# Panel.net
KiCad netlist of a schematic drawn in Altium Designer
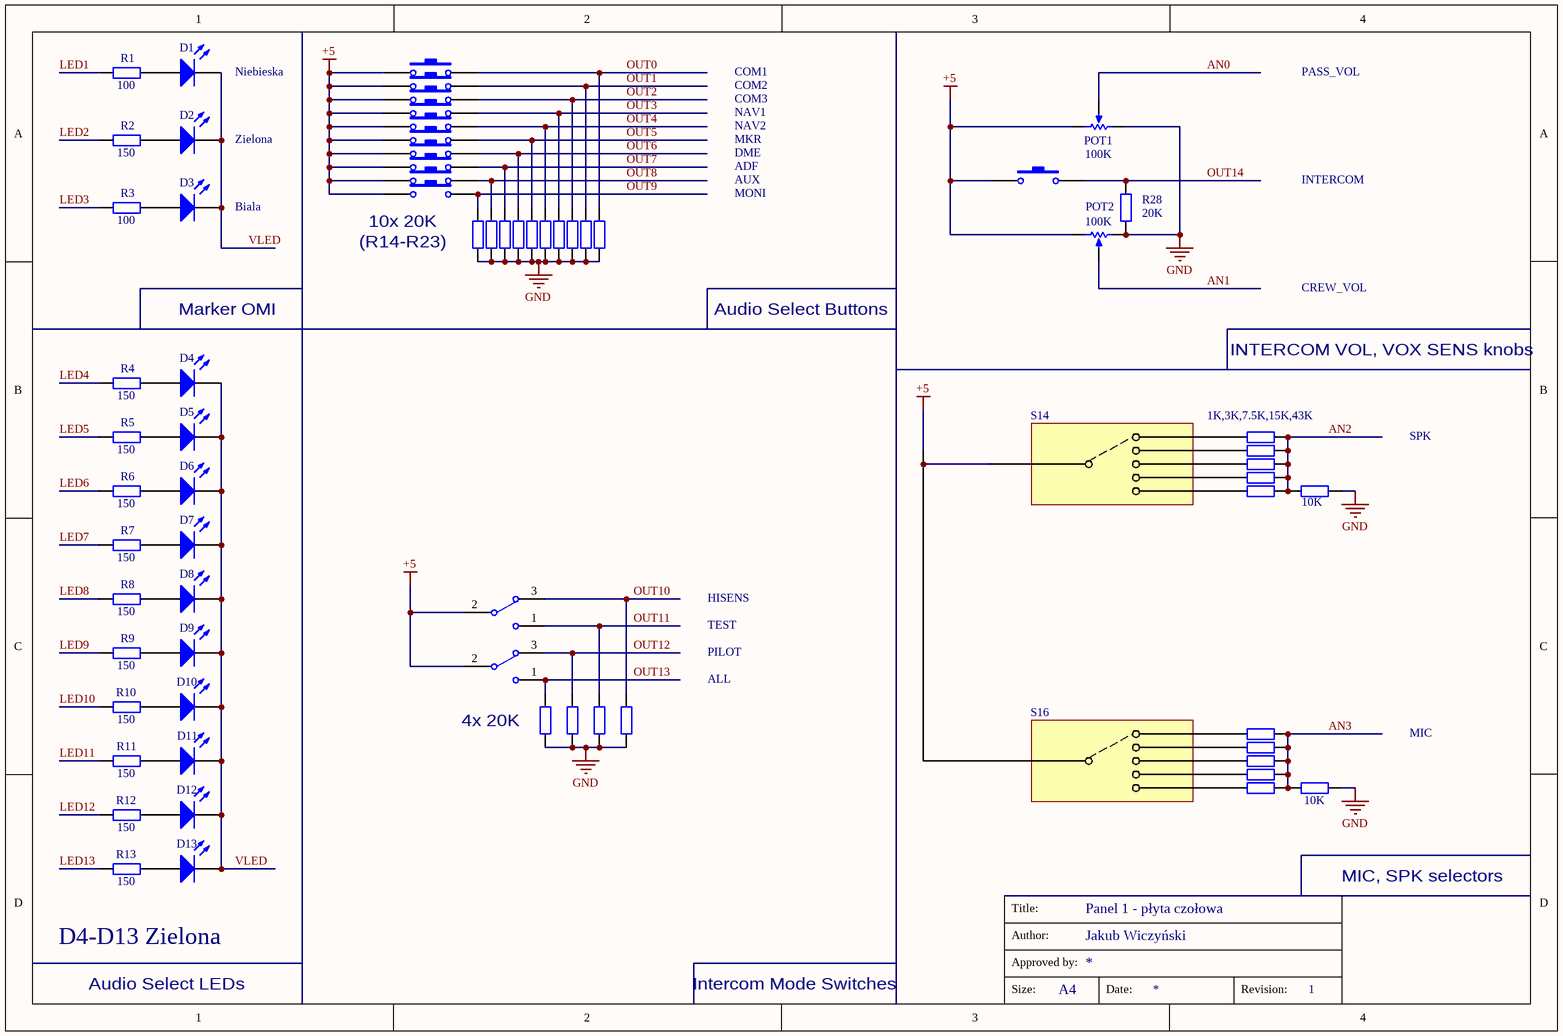
[diagram p0: Panel.SchDoc]

(export (version "E")
  (design (tool "Eeschema 10.0.6"))
  (components
    (comp (ref "D1")
      (value "http://www.tme.eu/pl/details/of-smd3216b/diody-led-smd-kolorowe/optoflash/")
      (footprint "Dioda SMD 1206 Niebieska")
      (description "LED SMD Niebieska")
      (fields (field (name "PUBLISHER") "Altium Limited"))
      (libsource (lib "Miscellaneous Devices") (part "LED0"))
    )
    (comp (ref "D2")
      (value "http://www.tme.eu/pl/details/of-smd3216yg-rv/diody-led-smd-kolorowe/optoflash/")
      (footprint "Dioda SMD 1206 Zielona")
      (description "LED SMD Zielona")
      (fields (field (name "PUBLISHER") "Altium Limited"))
      (libsource (lib "Miscellaneous Devices") (part "LED0"))
    )
    (comp (ref "D3")
      (value "http://www.tme.eu/pl/details/ltw-150tk/diody-led-smd-biale/liteon/")
      (footprint "Dioda SMD 1206 Biala")
      (description "LED SMD Biala")
      (fields (field (name "PUBLISHER") "Altium Limited"))
      (libsource (lib "Miscellaneous Devices") (part "LED0"))
    )
    (comp (ref "D4")
      (value "http://www.tme.eu/pl/details/of-smd3216yg-rv/diody-led-smd-kolorowe/optoflash/")
      (footprint "Dioda SMD 1206 Zielona")
      (description "LED SMD Zielona")
      (fields (field (name "PUBLISHER") "Altium Limited"))
      (libsource (lib "Miscellaneous Devices") (part "LED0"))
    )
    (comp (ref "D5")
      (value "http://www.tme.eu/pl/details/of-smd3216yg-rv/diody-led-smd-kolorowe/optoflash/")
      (footprint "Dioda SMD 1206 Zielona")
      (description "LED SMD Zielona")
      (fields (field (name "PUBLISHER") "Altium Limited"))
      (libsource (lib "Miscellaneous Devices") (part "LED0"))
    )
    (comp (ref "D6")
      (value "http://www.tme.eu/pl/details/of-smd3216yg-rv/diody-led-smd-kolorowe/optoflash/")
      (footprint "Dioda SMD 1206 Zielona")
      (description "LED SMD Zielona")
      (fields (field (name "PUBLISHER") "Altium Limited"))
      (libsource (lib "Miscellaneous Devices") (part "LED0"))
    )
    (comp (ref "D7")
      (value "http://www.tme.eu/pl/details/of-smd3216yg-rv/diody-led-smd-kolorowe/optoflash/")
      (footprint "Dioda SMD 1206 Zielona")
      (description "LED SMD Zielona")
      (fields (field (name "PUBLISHER") "Altium Limited"))
      (libsource (lib "Miscellaneous Devices") (part "LED0"))
    )
    (comp (ref "D8")
      (value "http://www.tme.eu/pl/details/of-smd3216yg-rv/diody-led-smd-kolorowe/optoflash/")
      (footprint "Dioda SMD 1206 Zielona")
      (description "LED SMD Zielona")
      (fields (field (name "PUBLISHER") "Altium Limited"))
      (libsource (lib "Miscellaneous Devices") (part "LED0"))
    )
    (comp (ref "D9")
      (value "http://www.tme.eu/pl/details/of-smd3216yg-rv/diody-led-smd-kolorowe/optoflash/")
      (footprint "Dioda SMD 1206 Zielona")
      (description "LED SMD Zielona")
      (fields (field (name "PUBLISHER") "Altium Limited"))
      (libsource (lib "Miscellaneous Devices") (part "LED0"))
    )
    (comp (ref "D10")
      (value "http://www.tme.eu/pl/details/of-smd3216yg-rv/diody-led-smd-kolorowe/optoflash/")
      (footprint "Dioda SMD 1206 Zielona")
      (description "LED SMD Zielona")
      (fields (field (name "PUBLISHER") "Altium Limited"))
      (libsource (lib "Miscellaneous Devices") (part "LED0"))
    )
    (comp (ref "D11")
      (value "http://www.tme.eu/pl/details/of-smd3216yg-rv/diody-led-smd-kolorowe/optoflash/")
      (footprint "Dioda SMD 1206 Zielona")
      (description "LED SMD Zielona")
      (fields (field (name "PUBLISHER") "Altium Limited"))
      (libsource (lib "Miscellaneous Devices") (part "LED0"))
    )
    (comp (ref "D12")
      (value "http://www.tme.eu/pl/details/of-smd3216yg-rv/diody-led-smd-kolorowe/optoflash/")
      (footprint "Dioda SMD 1206 Zielona")
      (description "LED SMD Zielona")
      (fields (field (name "PUBLISHER") "Altium Limited"))
      (libsource (lib "Miscellaneous Devices") (part "LED0"))
    )
    (comp (ref "D13")
      (value "http://www.tme.eu/pl/details/of-smd3216yg-rv/diody-led-smd-kolorowe/optoflash/")
      (footprint "Dioda SMD 1206 Zielona")
      (description "LED SMD Zielona")
      (fields (field (name "PUBLISHER") "Altium Limited"))
      (libsource (lib "Miscellaneous Devices") (part "LED0"))
    )
    (comp (ref "POT1")
      (value "100K")
      (footprint "Potentiometer")
      (description "Potencjometr 100K")
      (fields
        (field (name "Comment") "http://www.tme.eu/pl/details/pcw1j-c24-bab104l/potencjometry-jednoobrz-przew-plastiku/bourns/")
        (field (name "PUBLISHER") "Altium Limited")
      )
      (libsource (lib "Miscellaneous Devices") (part "RPot"))
    )
    (comp (ref "POT2")
      (value "100K")
      (footprint "Potentiometer")
      (description "Potencjometr 100K")
      (fields
        (field (name "Comment") "http://www.tme.eu/pl/details/pcw1j-c24-bab104l/potencjometry-jednoobrz-przew-plastiku/bourns/")
        (field (name "PUBLISHER") "Altium Limited")
      )
      (libsource (lib "Miscellaneous Devices") (part "RPot"))
    )
    (comp (ref "R1")
      (value "100")
      (footprint "C1206")
      (description "100R")
      (fields
        (field (name "Comment") "http://www.tme.eu/pl/details/crcw1206100rfktabc/rezystory-smd-1206/vishay/")
        (field (name "PUBLISHER") "Altium Limited")
      )
      (libsource (lib "Miscellaneous Devices") (part "Res2"))
    )
    (comp (ref "R2")
      (value "150")
      (footprint "C1206")
      (description "150R")
      (fields
        (field (name "Comment") "http://www.tme.eu/pl/details/crcw1206150rfktabc/rezystory-smd-1206/vishay/")
        (field (name "PUBLISHER") "Altium Limited")
      )
      (libsource (lib "Miscellaneous Devices") (part "Res2"))
    )
    (comp (ref "R3")
      (value "100")
      (footprint "C1206")
      (description "100R")
      (fields
        (field (name "Comment") "http://www.tme.eu/pl/details/crcw1206100rfktabc/rezystory-smd-1206/vishay/")
        (field (name "PUBLISHER") "Altium Limited")
      )
      (libsource (lib "Miscellaneous Devices") (part "Res2"))
    )
    (comp (ref "R4")
      (value "150")
      (footprint "C1206")
      (description "150R")
      (fields
        (field (name "Comment") "http://www.tme.eu/pl/details/crcw1206150rfktabc/rezystory-smd-1206/vishay/")
        (field (name "PUBLISHER") "Altium Limited")
      )
      (libsource (lib "Miscellaneous Devices") (part "Res2"))
    )
    (comp (ref "R5")
      (value "150")
      (footprint "C1206")
      (description "150R")
      (fields
        (field (name "Comment") "http://www.tme.eu/pl/details/crcw1206150rfktabc/rezystory-smd-1206/vishay/")
        (field (name "PUBLISHER") "Altium Limited")
      )
      (libsource (lib "Miscellaneous Devices") (part "Res2"))
    )
    (comp (ref "R6")
      (value "150")
      (footprint "C1206")
      (description "150R")
      (fields
        (field (name "Comment") "http://www.tme.eu/pl/details/crcw1206150rfktabc/rezystory-smd-1206/vishay/")
        (field (name "PUBLISHER") "Altium Limited")
      )
      (libsource (lib "Miscellaneous Devices") (part "Res2"))
    )
    (comp (ref "R7")
      (value "150")
      (footprint "C1206")
      (description "150R")
      (fields
        (field (name "Comment") "http://www.tme.eu/pl/details/crcw1206150rfktabc/rezystory-smd-1206/vishay/")
        (field (name "PUBLISHER") "Altium Limited")
      )
      (libsource (lib "Miscellaneous Devices") (part "Res2"))
    )
    (comp (ref "R8")
      (value "150")
      (footprint "C1206")
      (description "150R")
      (fields
        (field (name "Comment") "http://www.tme.eu/pl/details/crcw1206150rfktabc/rezystory-smd-1206/vishay/")
        (field (name "PUBLISHER") "Altium Limited")
      )
      (libsource (lib "Miscellaneous Devices") (part "Res2"))
    )
    (comp (ref "R9")
      (value "150")
      (footprint "C1206")
      (description "150R")
      (fields
        (field (name "Comment") "http://www.tme.eu/pl/details/crcw1206150rfktabc/rezystory-smd-1206/vishay/")
        (field (name "PUBLISHER") "Altium Limited")
      )
      (libsource (lib "Miscellaneous Devices") (part "Res2"))
    )
    (comp (ref "R10")
      (value "150")
      (footprint "C1206")
      (description "150R")
      (fields
        (field (name "Comment") "http://www.tme.eu/pl/details/crcw1206150rfktabc/rezystory-smd-1206/vishay/")
        (field (name "PUBLISHER") "Altium Limited")
      )
      (libsource (lib "Miscellaneous Devices") (part "Res2"))
    )
    (comp (ref "R11")
      (value "150")
      (footprint "C1206")
      (description "150R")
      (fields
        (field (name "Comment") "http://www.tme.eu/pl/details/crcw1206150rfktabc/rezystory-smd-1206/vishay/")
        (field (name "PUBLISHER") "Altium Limited")
      )
      (libsource (lib "Miscellaneous Devices") (part "Res2"))
    )
    (comp (ref "R12")
      (value "150")
      (footprint "C1206")
      (description "150R")
      (fields
        (field (name "Comment") "http://www.tme.eu/pl/details/crcw1206150rfktabc/rezystory-smd-1206/vishay/")
        (field (name "PUBLISHER") "Altium Limited")
      )
      (libsource (lib "Miscellaneous Devices") (part "Res2"))
    )
    (comp (ref "R13")
      (value "150")
      (footprint "C1206")
      (description "150R")
      (fields
        (field (name "Comment") "http://www.tme.eu/pl/details/crcw1206150rfktabc/rezystory-smd-1206/vishay/")
        (field (name "PUBLISHER") "Altium Limited")
      )
      (libsource (lib "Miscellaneous Devices") (part "Res2"))
    )
    (comp (ref "R14")
      (value "http://www.tme.eu/pl/details/crcw120620k0fktabc/rezystory-smd-1206/vishay/")
      (footprint "C1206")
      (description "20K")
      (fields (field (name "PUBLISHER") "Altium Limited"))
      (libsource (lib "") (part "Res2_1"))
    )
    (comp (ref "R15")
      (value "http://www.tme.eu/pl/details/crcw120620k0fktabc/rezystory-smd-1206/vishay/")
      (footprint "C1206")
      (description "20K")
      (fields (field (name "PUBLISHER") "Altium Limited"))
      (libsource (lib "") (part "Res2_1"))
    )
    (comp (ref "R16")
      (value "http://www.tme.eu/pl/details/crcw120620k0fktabc/rezystory-smd-1206/vishay/")
      (footprint "C1206")
      (description "20K")
      (fields (field (name "PUBLISHER") "Altium Limited"))
      (libsource (lib "") (part "Res2_1"))
    )
    (comp (ref "R17")
      (value "http://www.tme.eu/pl/details/crcw120620k0fktabc/rezystory-smd-1206/vishay/")
      (footprint "C1206")
      (description "20K")
      (fields (field (name "PUBLISHER") "Altium Limited"))
      (libsource (lib "") (part "Res2_1"))
    )
    (comp (ref "R18")
      (value "http://www.tme.eu/pl/details/crcw120620k0fktabc/rezystory-smd-1206/vishay/")
      (footprint "C1206")
      (description "20K")
      (fields (field (name "PUBLISHER") "Altium Limited"))
      (libsource (lib "") (part "Res2_1"))
    )
    (comp (ref "R19")
      (value "http://www.tme.eu/pl/details/crcw120620k0fktabc/rezystory-smd-1206/vishay/")
      (footprint "C1206")
      (description "20K")
      (fields (field (name "PUBLISHER") "Altium Limited"))
      (libsource (lib "") (part "Res2_1"))
    )
    (comp (ref "R20")
      (value "http://www.tme.eu/pl/details/crcw120620k0fktabc/rezystory-smd-1206/vishay/")
      (footprint "C1206")
      (description "20K")
      (fields (field (name "PUBLISHER") "Altium Limited"))
      (libsource (lib "") (part "Res2_1"))
    )
    (comp (ref "R21")
      (value "http://www.tme.eu/pl/details/crcw120620k0fktabc/rezystory-smd-1206/vishay/")
      (footprint "C1206")
      (description "20K")
      (fields (field (name "PUBLISHER") "Altium Limited"))
      (libsource (lib "") (part "Res2_1"))
    )
    (comp (ref "R22")
      (value "http://www.tme.eu/pl/details/crcw120620k0fktabc/rezystory-smd-1206/vishay/")
      (footprint "C1206")
      (description "20K")
      (fields (field (name "PUBLISHER") "Altium Limited"))
      (libsource (lib "") (part "Res2_1"))
    )
    (comp (ref "R23")
      (value "http://www.tme.eu/pl/details/crcw120620k0fktabc/rezystory-smd-1206/vishay/")
      (footprint "C1206")
      (description "20K")
      (fields (field (name "PUBLISHER") "Altium Limited"))
      (libsource (lib "") (part "Res2_1"))
    )
    (comp (ref "R24")
      (value "http://www.tme.eu/pl/details/crcw120620k0fktabc/rezystory-smd-1206/vishay/")
      (footprint "C1206")
      (description "20K")
      (fields (field (name "PUBLISHER") "Altium Limited"))
      (libsource (lib "") (part "Res2_1"))
    )
    (comp (ref "R25")
      (value "http://www.tme.eu/pl/details/crcw120620k0fktabc/rezystory-smd-1206/vishay/")
      (footprint "C1206")
      (description "20K")
      (fields (field (name "PUBLISHER") "Altium Limited"))
      (libsource (lib "") (part "Res2_1"))
    )
    (comp (ref "R26")
      (value "http://www.tme.eu/pl/details/crcw120620k0fktabc/rezystory-smd-1206/vishay/")
      (footprint "C1206")
      (description "20K")
      (fields (field (name "PUBLISHER") "Altium Limited"))
      (libsource (lib "") (part "Res2_1"))
    )
    (comp (ref "R27")
      (value "http://www.tme.eu/pl/details/crcw120620k0fktabc/rezystory-smd-1206/vishay/")
      (footprint "C1206")
      (description "20K")
      (fields (field (name "PUBLISHER") "Altium Limited"))
      (libsource (lib "") (part "Res2_1"))
    )
    (comp (ref "R28")
      (value "20K")
      (footprint "C1206")
      (fields
        (field (name "Comment") "http://www.tme.eu/pl/details/crcw120620k0fktabc/rezystory-smd-1206/vishay/")
        (field (name "PUBLISHER") "Altium Limited")
      )
      (libsource (lib "") (part "Res2_3"))
    )
    (comp (ref "R29")
      (value "http://www.tme.eu/pl/details/crcw12061k00fkea/rezystory-smd-1206/vishay/")
      (footprint "C1206")
      (description "1K")
      (fields (field (name "PUBLISHER") "Altium Limited"))
      (libsource (lib "Miscellaneous Devices") (part "Res2"))
    )
    (comp (ref "R30")
      (value "http://www.tme.eu/pl/details/crcw12063k00fktabc/rezystory-smd-1206/vishay/")
      (footprint "C1206")
      (description "3K")
      (fields (field (name "PUBLISHER") "Altium Limited"))
      (libsource (lib "Miscellaneous Devices") (part "Res2"))
    )
    (comp (ref "R31")
      (value "http://www.tme.eu/pl/details/crcw12067k50fktabc/rezystory-smd-1206/vishay/")
      (footprint "C1206")
      (description "7.5K")
      (fields (field (name "PUBLISHER") "Altium Limited"))
      (libsource (lib "Miscellaneous Devices") (part "Res2"))
    )
    (comp (ref "R32")
      (value "http://www.tme.eu/pl/details/crcw120615k0jntabc/rezystory-smd-1206/vishay/")
      (footprint "C1206")
      (description "15K")
      (fields (field (name "PUBLISHER") "Altium Limited"))
      (libsource (lib "Miscellaneous Devices") (part "Res2"))
    )
    (comp (ref "R33")
      (value "http://www.tme.eu/pl/details/rc1206jr-0743k/rezystory-smd-1206/yageo/rc1206jr-0743kl/")
      (footprint "C1206")
      (description "43K")
      (fields (field (name "PUBLISHER") "Altium Limited"))
      (libsource (lib "Miscellaneous Devices") (part "Res2"))
    )
    (comp (ref "R34")
      (value "10K")
      (footprint "C1206")
      (fields
        (field (name "Comment") "http://www.tme.eu/pl/details/crcw120610k0jntabc/rezystory-smd-1206/vishay/")
        (field (name "PUBLISHER") "Altium Limited")
      )
      (libsource (lib "") (part "Res2_2"))
    )
    (comp (ref "R36")
      (value "http://www.tme.eu/pl/details/crcw12061k00fkea/rezystory-smd-1206/vishay/")
      (footprint "C1206")
      (description "1K")
      (fields (field (name "PUBLISHER") "Altium Limited"))
      (libsource (lib "Miscellaneous Devices") (part "Res2"))
    )
    (comp (ref "R37")
      (value "http://www.tme.eu/pl/details/crcw12063k00fktabc/rezystory-smd-1206/vishay/")
      (footprint "C1206")
      (description "3K")
      (fields (field (name "PUBLISHER") "Altium Limited"))
      (libsource (lib "Miscellaneous Devices") (part "Res2"))
    )
    (comp (ref "R38")
      (value "http://www.tme.eu/pl/details/crcw12067k50fktabc/rezystory-smd-1206/vishay/")
      (footprint "C1206")
      (description "7.5K")
      (fields (field (name "PUBLISHER") "Altium Limited"))
      (libsource (lib "Miscellaneous Devices") (part "Res2"))
    )
    (comp (ref "R39")
      (value "http://www.tme.eu/pl/details/crcw120615k0jntabc/rezystory-smd-1206/vishay/")
      (footprint "C1206")
      (description "15K")
      (fields (field (name "PUBLISHER") "Altium Limited"))
      (libsource (lib "Miscellaneous Devices") (part "Res2"))
    )
    (comp (ref "R40")
      (value "http://www.tme.eu/pl/details/rc1206jr-0743k/rezystory-smd-1206/yageo/rc1206jr-0743kl/")
      (footprint "C1206")
      (description "43K")
      (fields (field (name "PUBLISHER") "Altium Limited"))
      (libsource (lib "Miscellaneous Devices") (part "Res2"))
    )
    (comp (ref "R41")
      (value "10K")
      (footprint "C1206")
      (fields
        (field (name "Comment") "http://www.tme.eu/pl/details/crcw120610k0jntabc/rezystory-smd-1206/vishay/")
        (field (name "PUBLISHER") "Altium Limited")
      )
      (libsource (lib "") (part "Res2_2"))
    )
    (comp (ref "S1")
      (value "http://www.tme.eu/pl/details/1301.9315/mikroprzelaczniki-tact-pcb/schurter/")
      (footprint "Microswitch_SMD")
      (description "Microswitch (SPST)")
      (fields (field (name "PUBLISHER") "Altium Limited"))
      (libsource (lib "Miscellaneous Devices") (part "SW-PB"))
    )
    (comp (ref "S2")
      (value "http://www.tme.eu/pl/details/1301.9315/mikroprzelaczniki-tact-pcb/schurter/")
      (footprint "Microswitch_SMD")
      (description "Microswitch (SPST)")
      (fields (field (name "PUBLISHER") "Altium Limited"))
      (libsource (lib "Miscellaneous Devices") (part "SW-PB"))
    )
    (comp (ref "S3")
      (value "http://www.tme.eu/pl/details/1301.9315/mikroprzelaczniki-tact-pcb/schurter/")
      (footprint "Microswitch_SMD")
      (description "Microswitch (SPST)")
      (fields (field (name "PUBLISHER") "Altium Limited"))
      (libsource (lib "Miscellaneous Devices") (part "SW-PB"))
    )
    (comp (ref "S4")
      (value "http://www.tme.eu/pl/details/1301.9315/mikroprzelaczniki-tact-pcb/schurter/")
      (footprint "Microswitch_SMD")
      (description "Microswitch (SPST)")
      (fields (field (name "PUBLISHER") "Altium Limited"))
      (libsource (lib "Miscellaneous Devices") (part "SW-PB"))
    )
    (comp (ref "S5")
      (value "http://www.tme.eu/pl/details/1301.9315/mikroprzelaczniki-tact-pcb/schurter/")
      (footprint "Microswitch_SMD")
      (description "Microswitch (SPST)")
      (fields (field (name "PUBLISHER") "Altium Limited"))
      (libsource (lib "Miscellaneous Devices") (part "SW-PB"))
    )
    (comp (ref "S6")
      (value "http://www.tme.eu/pl/details/1301.9315/mikroprzelaczniki-tact-pcb/schurter/")
      (footprint "Microswitch_SMD")
      (description "Microswitch (SPST)")
      (fields (field (name "PUBLISHER") "Altium Limited"))
      (libsource (lib "Miscellaneous Devices") (part "SW-PB"))
    )
    (comp (ref "S7")
      (value "http://www.tme.eu/pl/details/1301.9315/mikroprzelaczniki-tact-pcb/schurter/")
      (footprint "Microswitch_SMD")
      (description "Microswitch (SPST)")
      (fields (field (name "PUBLISHER") "Altium Limited"))
      (libsource (lib "Miscellaneous Devices") (part "SW-PB"))
    )
    (comp (ref "S8")
      (value "http://www.tme.eu/pl/details/1301.9315/mikroprzelaczniki-tact-pcb/schurter/")
      (footprint "Microswitch_SMD")
      (description "Microswitch (SPST)")
      (fields (field (name "PUBLISHER") "Altium Limited"))
      (libsource (lib "Miscellaneous Devices") (part "SW-PB"))
    )
    (comp (ref "S9")
      (value "http://www.tme.eu/pl/details/1301.9315/mikroprzelaczniki-tact-pcb/schurter/")
      (footprint "Microswitch_SMD")
      (description "Microswitch (SPST)")
      (fields (field (name "PUBLISHER") "Altium Limited"))
      (libsource (lib "Miscellaneous Devices") (part "SW-PB"))
    )
    (comp (ref "S10")
      (value "http://www.tme.eu/pl/details/1301.9315/mikroprzelaczniki-tact-pcb/schurter/")
      (footprint "Microswitch_SMD")
      (description "Microswitch (SPST)")
      (fields (field (name "PUBLISHER") "Altium Limited"))
      (libsource (lib "Miscellaneous Devices") (part "SW-PB"))
    )
    (comp (ref "S11")
      (value "http://www.tme.eu/pl/details/1ms3t1b1m1qe/przelaczniki-dzwigniowe/ninigi/")
      (footprint "3POS SWITCH")
      (description "Przelacznik SP3T")
      (fields (field (name "PUBLISHER") "Altium Limited"))
      (libsource (lib "Miscellaneous Devices") (part "SW-SPDT"))
    )
    (comp (ref "S12")
      (value "http://www.tme.eu/pl/details/1ms3t1b1m1qe/przelaczniki-dzwigniowe/ninigi/")
      (footprint "3POS SWITCH")
      (description "Przelacznik SP3T")
      (fields (field (name "PUBLISHER") "Altium Limited"))
      (libsource (lib "Miscellaneous Devices") (part "SW-SPDT"))
    )
    (comp (ref "S13")
      (value "http://www.tme.eu/pl/details/1301.9315/mikroprzelaczniki-tact-pcb/schurter/")
      (footprint "Microswitch_SMD")
      (description "Microswitch (SPST)")
      (fields (field (name "PUBLISHER") "Altium Limited"))
      (libsource (lib "Miscellaneous Devices") (part "SW-PB"))
    )
    (comp (ref "S14")
      (value "http://www.tme.eu/pl/details/sr2611515fn/przelaczniki-obrotowe/ninigi/")
      (footprint "ROT SW")
      (description "Przelacznik obrotowy 5-pozycyjny")
      (libsource (lib "pot_sw") (part "5SW"))
    )
    (comp (ref "S16")
      (value "http://www.tme.eu/pl/details/sr2611515fn/przelaczniki-obrotowe/ninigi/")
      (footprint "ROT SW")
      (description "Przelacznik obrotowy 5-pozycyjny")
      (libsource (lib "pot_sw") (part "5SW"))
    )
  )
  (nets
    (net (code "1") (name "+5") (class "Default")
      (node (ref "POT1") (pin "2") (pinfunction "BOT_2") (pintype "passive"))
      (node (ref "POT2") (pin "1") (pinfunction "TOP_1") (pintype "passive"))
      (node (ref "S1") (pin "1") (pinfunction "1_1") (pintype "passive"))
      (node (ref "S10") (pin "1") (pinfunction "1_1") (pintype "passive"))
      (node (ref "S11") (pin "2") (pinfunction "2_2") (pintype "passive"))
      (node (ref "S12") (pin "2") (pinfunction "2_2") (pintype "passive"))
      (node (ref "S13") (pin "1") (pinfunction "1_1") (pintype "passive"))
      (node (ref "S14") (pin "1") (pinfunction "1_1") (pintype "passive"))
      (node (ref "S16") (pin "1") (pinfunction "1_1") (pintype "passive"))
      (node (ref "S2") (pin "1") (pinfunction "1_1") (pintype "passive"))
      (node (ref "S3") (pin "1") (pinfunction "1_1") (pintype "passive"))
      (node (ref "S4") (pin "1") (pinfunction "1_1") (pintype "passive"))
      (node (ref "S5") (pin "1") (pinfunction "1_1") (pintype "passive"))
      (node (ref "S6") (pin "1") (pinfunction "1_1") (pintype "passive"))
      (node (ref "S7") (pin "1") (pinfunction "1_1") (pintype "passive"))
      (node (ref "S8") (pin "1") (pinfunction "1_1") (pintype "passive"))
      (node (ref "S9") (pin "1") (pinfunction "1_1") (pintype "passive"))
    )
    (net (code "2") (name "/AN0") (class "Default")
      (node (ref "POT1") (pin "3") (pinfunction "TAP_3") (pintype "passive"))
    )
    (net (code "3") (name "/AN1") (class "Default")
      (node (ref "POT2") (pin "3") (pinfunction "TAP_3") (pintype "passive"))
    )
    (net (code "4") (name "/AN2") (class "Default")
      (node (ref "R29") (pin "2") (pinfunction "2_2") (pintype "passive"))
      (node (ref "R30") (pin "2") (pinfunction "2_2") (pintype "passive"))
      (node (ref "R31") (pin "2") (pinfunction "2_2") (pintype "passive"))
      (node (ref "R32") (pin "2") (pinfunction "2_2") (pintype "passive"))
      (node (ref "R33") (pin "2") (pinfunction "2_2") (pintype "passive"))
      (node (ref "R34") (pin "2") (pinfunction "2_2") (pintype "passive"))
    )
    (net (code "5") (name "/AN3") (class "Default")
      (node (ref "R36") (pin "2") (pinfunction "2_2") (pintype "passive"))
      (node (ref "R37") (pin "2") (pinfunction "2_2") (pintype "passive"))
      (node (ref "R38") (pin "2") (pinfunction "2_2") (pintype "passive"))
      (node (ref "R39") (pin "2") (pinfunction "2_2") (pintype "passive"))
      (node (ref "R40") (pin "2") (pinfunction "2_2") (pintype "passive"))
      (node (ref "R41") (pin "2") (pinfunction "2_2") (pintype "passive"))
    )
    (net (code "6") (name "/LED1") (class "Default")
      (node (ref "R1") (pin "1") (pinfunction "1_1") (pintype "passive"))
    )
    (net (code "7") (name "/LED2") (class "Default")
      (node (ref "R2") (pin "1") (pinfunction "1_1") (pintype "passive"))
    )
    (net (code "8") (name "/LED3") (class "Default")
      (node (ref "R3") (pin "1") (pinfunction "1_1") (pintype "passive"))
    )
    (net (code "9") (name "/LED4") (class "Default")
      (node (ref "R4") (pin "1") (pinfunction "1_1") (pintype "passive"))
    )
    (net (code "10") (name "/LED5") (class "Default")
      (node (ref "R5") (pin "1") (pinfunction "1_1") (pintype "passive"))
    )
    (net (code "11") (name "/LED6") (class "Default")
      (node (ref "R6") (pin "1") (pinfunction "1_1") (pintype "passive"))
    )
    (net (code "12") (name "/LED7") (class "Default")
      (node (ref "R7") (pin "1") (pinfunction "1_1") (pintype "passive"))
    )
    (net (code "13") (name "/LED8") (class "Default")
      (node (ref "R8") (pin "1") (pinfunction "1_1") (pintype "passive"))
    )
    (net (code "14") (name "/LED9") (class "Default")
      (node (ref "R9") (pin "1") (pinfunction "1_1") (pintype "passive"))
    )
    (net (code "15") (name "/LED10") (class "Default")
      (node (ref "R10") (pin "1") (pinfunction "1_1") (pintype "passive"))
    )
    (net (code "16") (name "/LED11") (class "Default")
      (node (ref "R11") (pin "1") (pinfunction "1_1") (pintype "passive"))
    )
    (net (code "17") (name "/LED12") (class "Default")
      (node (ref "R12") (pin "1") (pinfunction "1_1") (pintype "passive"))
    )
    (net (code "18") (name "/LED13") (class "Default")
      (node (ref "R13") (pin "1") (pinfunction "1_1") (pintype "passive"))
    )
    (net (code "19") (name "/OUT0") (class "Default")
      (node (ref "R23") (pin "2") (pinfunction "2_2") (pintype "passive"))
      (node (ref "S1") (pin "2") (pinfunction "2_2") (pintype "passive"))
    )
    (net (code "20") (name "/OUT1") (class "Default")
      (node (ref "R22") (pin "2") (pinfunction "2_2") (pintype "passive"))
      (node (ref "S2") (pin "2") (pinfunction "2_2") (pintype "passive"))
    )
    (net (code "21") (name "/OUT2") (class "Default")
      (node (ref "R21") (pin "2") (pinfunction "2_2") (pintype "passive"))
      (node (ref "S3") (pin "2") (pinfunction "2_2") (pintype "passive"))
    )
    (net (code "22") (name "/OUT3") (class "Default")
      (node (ref "R20") (pin "2") (pinfunction "2_2") (pintype "passive"))
      (node (ref "S4") (pin "2") (pinfunction "2_2") (pintype "passive"))
    )
    (net (code "23") (name "/OUT4") (class "Default")
      (node (ref "R19") (pin "2") (pinfunction "2_2") (pintype "passive"))
      (node (ref "S5") (pin "2") (pinfunction "2_2") (pintype "passive"))
    )
    (net (code "24") (name "/OUT5") (class "Default")
      (node (ref "R18") (pin "2") (pinfunction "2_2") (pintype "passive"))
      (node (ref "S6") (pin "2") (pinfunction "2_2") (pintype "passive"))
    )
    (net (code "25") (name "/OUT6") (class "Default")
      (node (ref "R17") (pin "2") (pinfunction "2_2") (pintype "passive"))
      (node (ref "S7") (pin "2") (pinfunction "2_2") (pintype "passive"))
    )
    (net (code "26") (name "/OUT7") (class "Default")
      (node (ref "R16") (pin "2") (pinfunction "2_2") (pintype "passive"))
      (node (ref "S8") (pin "2") (pinfunction "2_2") (pintype "passive"))
    )
    (net (code "27") (name "/OUT8") (class "Default")
      (node (ref "R15") (pin "2") (pinfunction "2_2") (pintype "passive"))
      (node (ref "S9") (pin "2") (pinfunction "2_2") (pintype "passive"))
    )
    (net (code "28") (name "/OUT9") (class "Default")
      (node (ref "R14") (pin "2") (pinfunction "2_2") (pintype "passive"))
      (node (ref "S10") (pin "2") (pinfunction "2_2") (pintype "passive"))
    )
    (net (code "29") (name "/OUT10") (class "Default")
      (node (ref "R27") (pin "2") (pinfunction "2_2") (pintype "passive"))
      (node (ref "S11") (pin "3") (pinfunction "3_3") (pintype "passive"))
    )
    (net (code "30") (name "/OUT11") (class "Default")
      (node (ref "R26") (pin "2") (pinfunction "2_2") (pintype "passive"))
      (node (ref "S11") (pin "1") (pinfunction "1_1") (pintype "passive"))
    )
    (net (code "31") (name "/OUT12") (class "Default")
      (node (ref "R25") (pin "2") (pinfunction "2_2") (pintype "passive"))
      (node (ref "S12") (pin "3") (pinfunction "3_3") (pintype "passive"))
    )
    (net (code "32") (name "/OUT13") (class "Default")
      (node (ref "R24") (pin "2") (pinfunction "2_2") (pintype "passive"))
      (node (ref "S12") (pin "1") (pinfunction "1_1") (pintype "passive"))
    )
    (net (code "33") (name "/OUT14") (class "Default")
      (node (ref "R28") (pin "1") (pinfunction "1_1") (pintype "passive"))
      (node (ref "S13") (pin "2") (pinfunction "2_2") (pintype "passive"))
    )
    (net (code "34") (name "/VLED") (class "Default")
      (node (ref "D1") (pin "2") (pinfunction "K_2") (pintype "passive"))
      (node (ref "D10") (pin "2") (pinfunction "K_2") (pintype "passive"))
      (node (ref "D11") (pin "2") (pinfunction "K_2") (pintype "passive"))
      (node (ref "D12") (pin "2") (pinfunction "K_2") (pintype "passive"))
      (node (ref "D13") (pin "2") (pinfunction "K_2") (pintype "passive"))
      (node (ref "D2") (pin "2") (pinfunction "K_2") (pintype "passive"))
      (node (ref "D3") (pin "2") (pinfunction "K_2") (pintype "passive"))
      (node (ref "D4") (pin "2") (pinfunction "K_2") (pintype "passive"))
      (node (ref "D5") (pin "2") (pinfunction "K_2") (pintype "passive"))
      (node (ref "D6") (pin "2") (pinfunction "K_2") (pintype "passive"))
      (node (ref "D7") (pin "2") (pinfunction "K_2") (pintype "passive"))
      (node (ref "D8") (pin "2") (pinfunction "K_2") (pintype "passive"))
      (node (ref "D9") (pin "2") (pinfunction "K_2") (pintype "passive"))
    )
    (net (code "35") (name "GND") (class "Default")
      (node (ref "POT1") (pin "1") (pinfunction "TOP_1") (pintype "passive"))
      (node (ref "POT2") (pin "2") (pinfunction "BOT_2") (pintype "passive"))
      (node (ref "R14") (pin "1") (pinfunction "1_1") (pintype "passive"))
      (node (ref "R15") (pin "1") (pinfunction "1_1") (pintype "passive"))
      (node (ref "R16") (pin "1") (pinfunction "1_1") (pintype "passive"))
      (node (ref "R17") (pin "1") (pinfunction "1_1") (pintype "passive"))
      (node (ref "R18") (pin "1") (pinfunction "1_1") (pintype "passive"))
      (node (ref "R19") (pin "1") (pinfunction "1_1") (pintype "passive"))
      (node (ref "R20") (pin "1") (pinfunction "1_1") (pintype "passive"))
      (node (ref "R21") (pin "1") (pinfunction "1_1") (pintype "passive"))
      (node (ref "R22") (pin "1") (pinfunction "1_1") (pintype "passive"))
      (node (ref "R23") (pin "1") (pinfunction "1_1") (pintype "passive"))
      (node (ref "R24") (pin "1") (pinfunction "1_1") (pintype "passive"))
      (node (ref "R25") (pin "1") (pinfunction "1_1") (pintype "passive"))
      (node (ref "R26") (pin "1") (pinfunction "1_1") (pintype "passive"))
      (node (ref "R27") (pin "1") (pinfunction "1_1") (pintype "passive"))
      (node (ref "R28") (pin "2") (pinfunction "2_2") (pintype "passive"))
      (node (ref "R34") (pin "1") (pinfunction "1_1") (pintype "passive"))
      (node (ref "R41") (pin "1") (pinfunction "1_1") (pintype "passive"))
    )
    (net (code "36") (name "Net-(D1-A)") (class "Default")
      (node (ref "D1") (pin "1") (pinfunction "A_1") (pintype "passive"))
      (node (ref "R1") (pin "2") (pinfunction "2_2") (pintype "passive"))
    )
    (net (code "37") (name "Net-(D2-A)") (class "Default")
      (node (ref "D2") (pin "1") (pinfunction "A_1") (pintype "passive"))
      (node (ref "R2") (pin "2") (pinfunction "2_2") (pintype "passive"))
    )
    (net (code "38") (name "Net-(D3-A)") (class "Default")
      (node (ref "D3") (pin "1") (pinfunction "A_1") (pintype "passive"))
      (node (ref "R3") (pin "2") (pinfunction "2_2") (pintype "passive"))
    )
    (net (code "39") (name "Net-(D4-A)") (class "Default")
      (node (ref "D4") (pin "1") (pinfunction "A_1") (pintype "passive"))
      (node (ref "R4") (pin "2") (pinfunction "2_2") (pintype "passive"))
    )
    (net (code "40") (name "Net-(D5-A)") (class "Default")
      (node (ref "D5") (pin "1") (pinfunction "A_1") (pintype "passive"))
      (node (ref "R5") (pin "2") (pinfunction "2_2") (pintype "passive"))
    )
    (net (code "41") (name "Net-(D6-A)") (class "Default")
      (node (ref "D6") (pin "1") (pinfunction "A_1") (pintype "passive"))
      (node (ref "R6") (pin "2") (pinfunction "2_2") (pintype "passive"))
    )
    (net (code "42") (name "Net-(D7-A)") (class "Default")
      (node (ref "D7") (pin "1") (pinfunction "A_1") (pintype "passive"))
      (node (ref "R7") (pin "2") (pinfunction "2_2") (pintype "passive"))
    )
    (net (code "43") (name "Net-(D8-A)") (class "Default")
      (node (ref "D8") (pin "1") (pinfunction "A_1") (pintype "passive"))
      (node (ref "R8") (pin "2") (pinfunction "2_2") (pintype "passive"))
    )
    (net (code "44") (name "Net-(D9-A)") (class "Default")
      (node (ref "D9") (pin "1") (pinfunction "A_1") (pintype "passive"))
      (node (ref "R9") (pin "2") (pinfunction "2_2") (pintype "passive"))
    )
    (net (code "45") (name "Net-(D10-A)") (class "Default")
      (node (ref "D10") (pin "1") (pinfunction "A_1") (pintype "passive"))
      (node (ref "R10") (pin "2") (pinfunction "2_2") (pintype "passive"))
    )
    (net (code "46") (name "Net-(D11-A)") (class "Default")
      (node (ref "D11") (pin "1") (pinfunction "A_1") (pintype "passive"))
      (node (ref "R11") (pin "2") (pinfunction "2_2") (pintype "passive"))
    )
    (net (code "47") (name "Net-(D12-A)") (class "Default")
      (node (ref "D12") (pin "1") (pinfunction "A_1") (pintype "passive"))
      (node (ref "R12") (pin "2") (pinfunction "2_2") (pintype "passive"))
    )
    (net (code "48") (name "Net-(D13-A)") (class "Default")
      (node (ref "D13") (pin "1") (pinfunction "A_1") (pintype "passive"))
      (node (ref "R13") (pin "2") (pinfunction "2_2") (pintype "passive"))
    )
    (net (code "49") (name "Net-(R29-Pad1)") (class "Default")
      (node (ref "R29") (pin "1") (pinfunction "1_1") (pintype "passive"))
      (node (ref "S14") (pin "2") (pinfunction "2_2") (pintype "passive"))
    )
    (net (code "50") (name "Net-(R30-Pad1)") (class "Default")
      (node (ref "R30") (pin "1") (pinfunction "1_1") (pintype "passive"))
      (node (ref "S14") (pin "3") (pinfunction "3_3") (pintype "passive"))
    )
    (net (code "51") (name "Net-(R31-Pad1)") (class "Default")
      (node (ref "R31") (pin "1") (pinfunction "1_1") (pintype "passive"))
      (node (ref "S14") (pin "4") (pinfunction "4_4") (pintype "passive"))
    )
    (net (code "52") (name "Net-(R32-Pad1)") (class "Default")
      (node (ref "R32") (pin "1") (pinfunction "1_1") (pintype "passive"))
      (node (ref "S14") (pin "5") (pinfunction "5_5") (pintype "passive"))
    )
    (net (code "53") (name "Net-(R33-Pad1)") (class "Default")
      (node (ref "R33") (pin "1") (pinfunction "1_1") (pintype "passive"))
      (node (ref "S14") (pin "6") (pinfunction "6_6") (pintype "passive"))
    )
    (net (code "54") (name "Net-(R36-Pad1)") (class "Default")
      (node (ref "R36") (pin "1") (pinfunction "1_1") (pintype "passive"))
      (node (ref "S16") (pin "2") (pinfunction "2_2") (pintype "passive"))
    )
    (net (code "55") (name "Net-(R37-Pad1)") (class "Default")
      (node (ref "R37") (pin "1") (pinfunction "1_1") (pintype "passive"))
      (node (ref "S16") (pin "3") (pinfunction "3_3") (pintype "passive"))
    )
    (net (code "56") (name "Net-(R38-Pad1)") (class "Default")
      (node (ref "R38") (pin "1") (pinfunction "1_1") (pintype "passive"))
      (node (ref "S16") (pin "4") (pinfunction "4_4") (pintype "passive"))
    )
    (net (code "57") (name "Net-(R39-Pad1)") (class "Default")
      (node (ref "R39") (pin "1") (pinfunction "1_1") (pintype "passive"))
      (node (ref "S16") (pin "5") (pinfunction "5_5") (pintype "passive"))
    )
    (net (code "58") (name "Net-(R40-Pad1)") (class "Default")
      (node (ref "R40") (pin "1") (pinfunction "1_1") (pintype "passive"))
      (node (ref "S16") (pin "6") (pinfunction "6_6") (pintype "passive"))
    )
  )
)
